# tdt_rereference.net
KiCad netlist of a schematic drawn in EAGLE
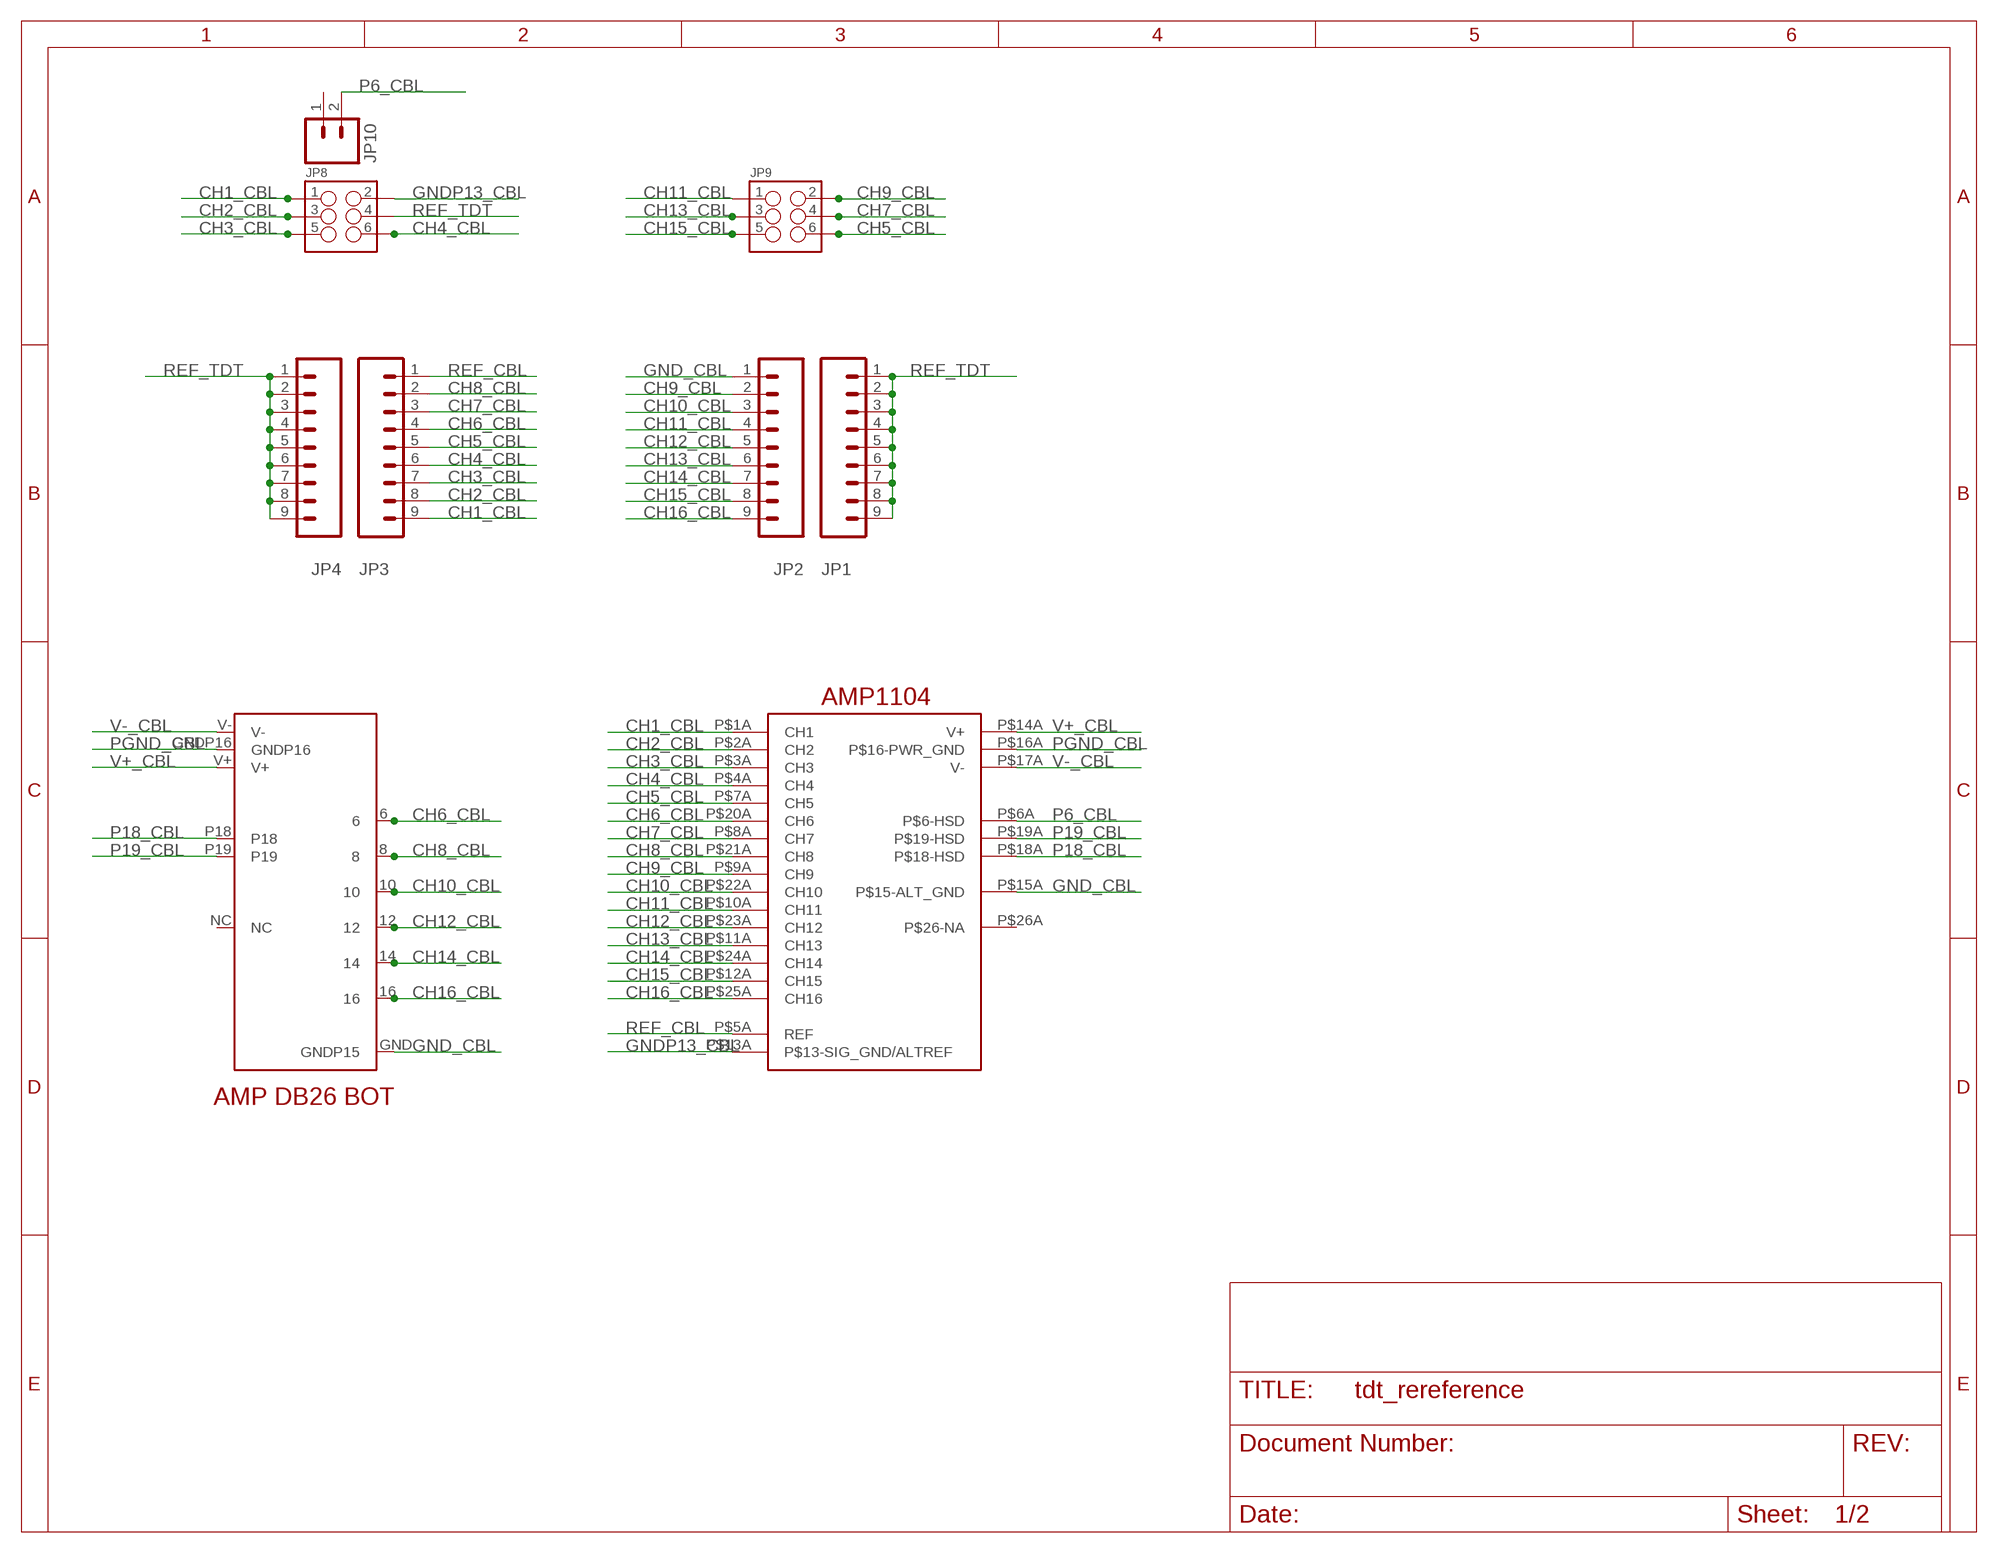
[diagram p0: schematic, sheet 1]
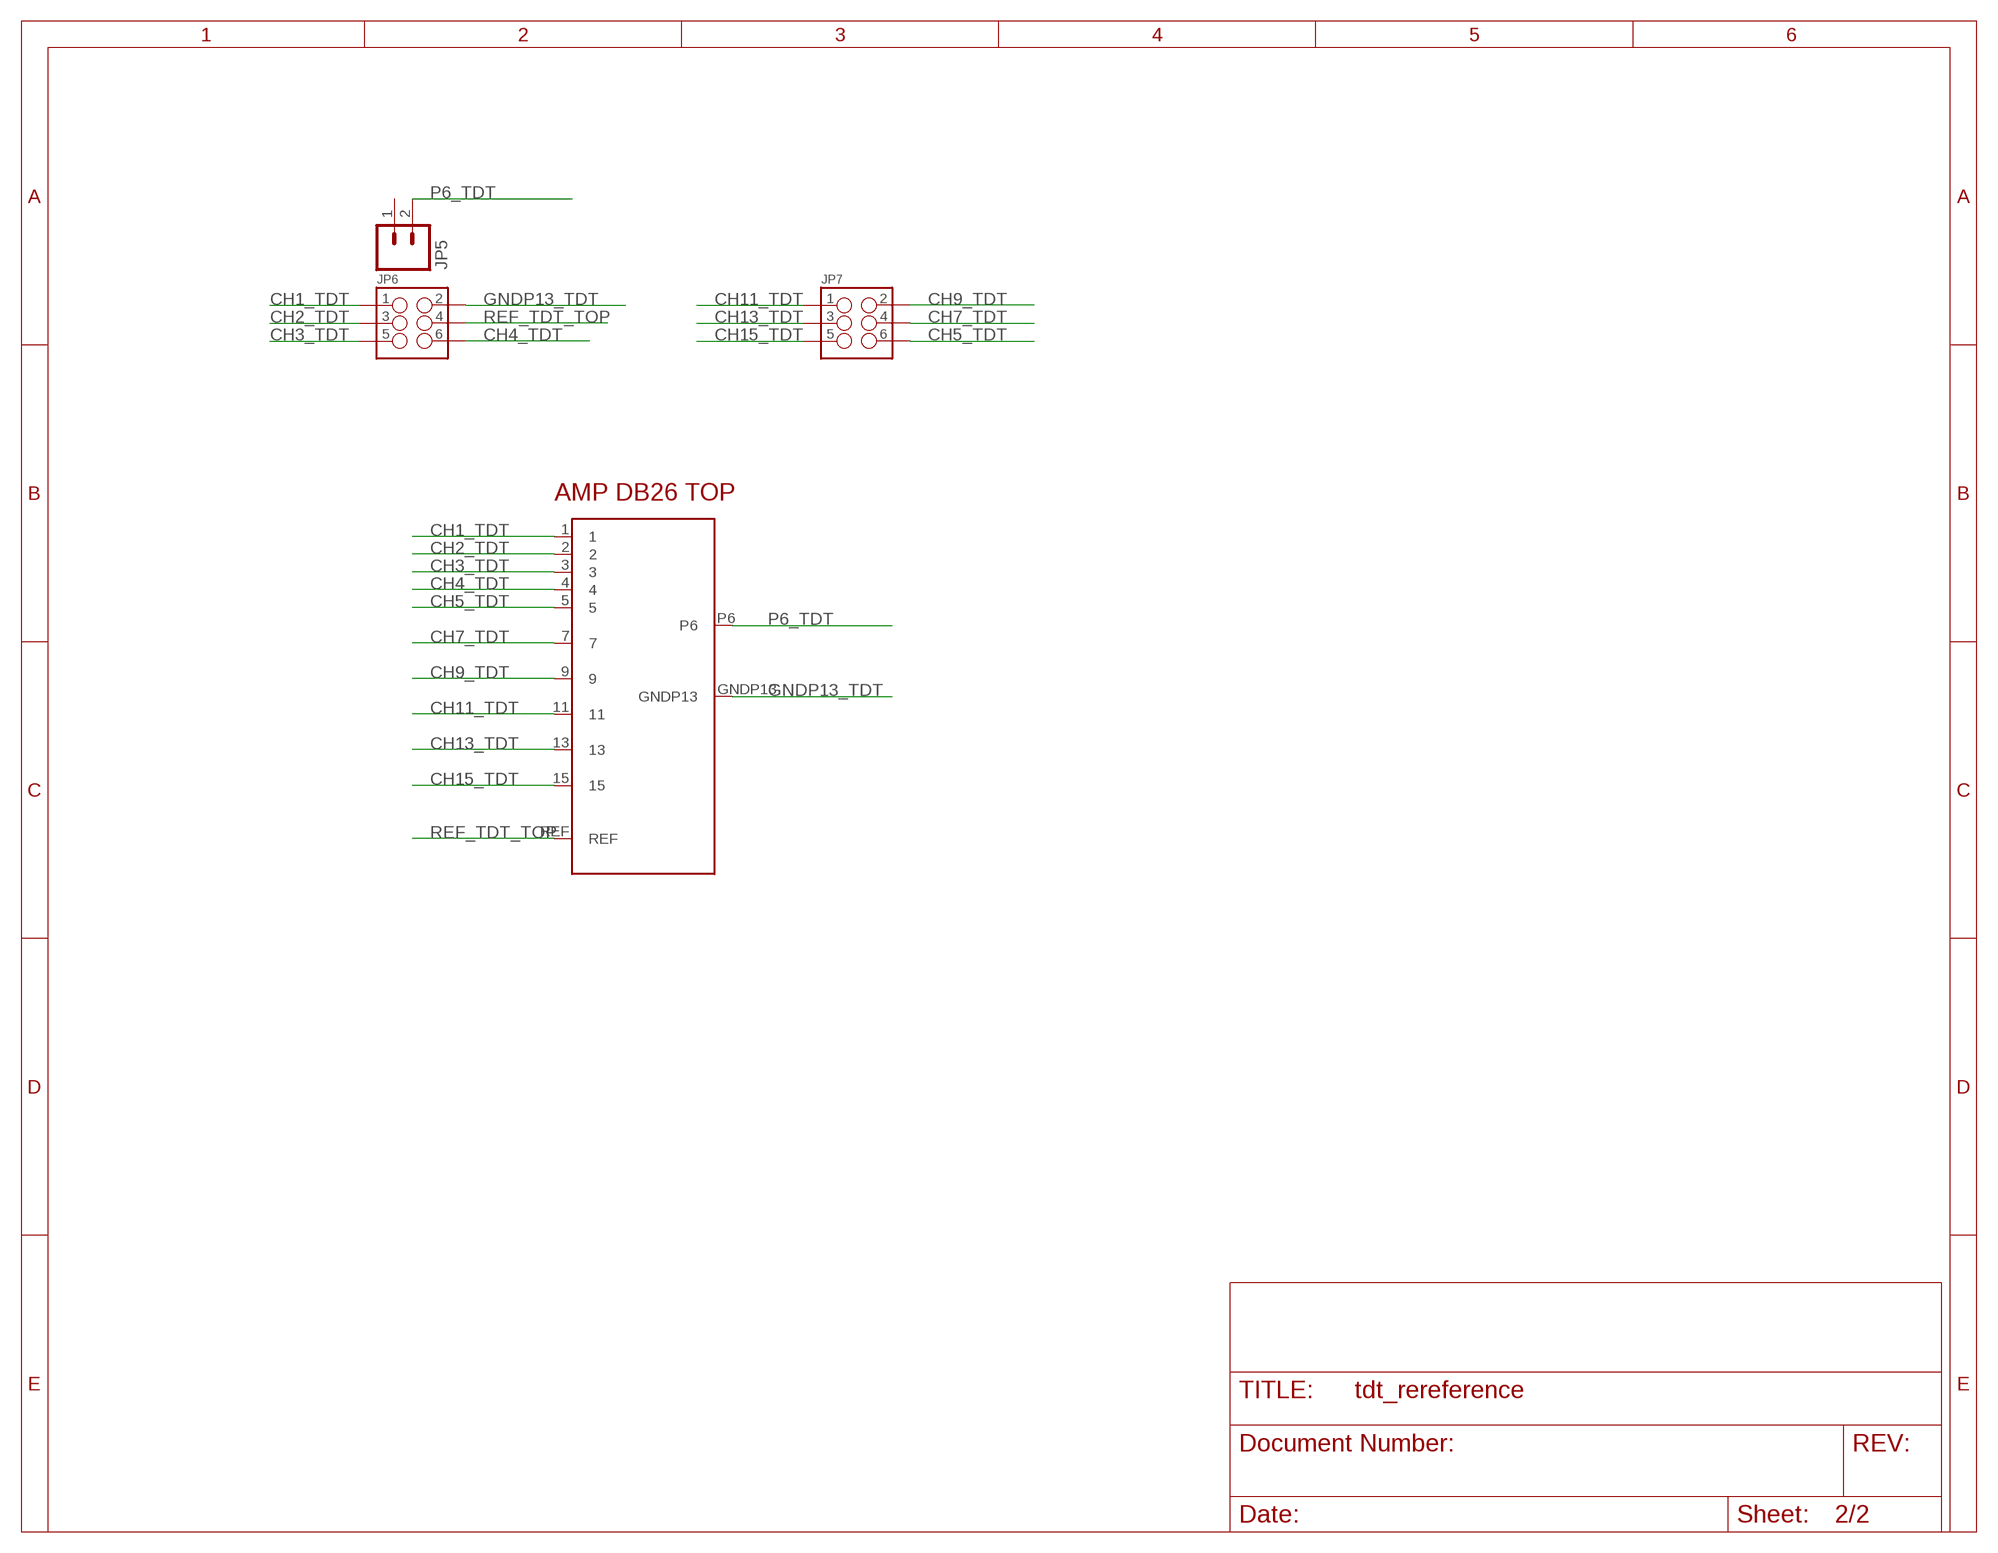
[diagram p1: schematic, sheet 2]

(export (version "E")
  (design (tool "Eeschema 10.0.6"))
  (components
    (comp (ref "JP5")
      (value "M02PTH")
      (footprint "eagle-import:1X02")
      (libsource (lib "eagle-import") (part "M02PTH"))
    )
    (comp (ref "JP6")
      (value "M03X22X3_SILK_MALE_PTH")
      (footprint "eagle-import:2X3")
      (libsource (lib "eagle-import") (part "M03X22X3_SILK_MALE_PTH"))
    )
    (comp (ref "JP7")
      (value "M03X22X3_SILK_MALE_PTH")
      (footprint "eagle-import:2X3")
      (libsource (lib "eagle-import") (part "M03X22X3_SILK_MALE_PTH"))
    )
    (comp (ref "U$2")
      (value "DB26-MALE-TOP")
      (footprint "eagle-import:DB26-MALE-TOP")
      (libsource (lib "eagle-import") (part "DB26-MALE-TOP"))
    )
    (comp (ref "JP1")
      (value "M09")
      (footprint "eagle-import:1X09")
      (libsource (lib "eagle-import") (part "M09"))
    )
    (comp (ref "JP2")
      (value "M09")
      (footprint "eagle-import:1X09")
      (libsource (lib "eagle-import") (part "M09"))
    )
    (comp (ref "JP3")
      (value "M09")
      (footprint "eagle-import:1X09")
      (libsource (lib "eagle-import") (part "M09"))
    )
    (comp (ref "JP4")
      (value "M09")
      (footprint "eagle-import:1X09")
      (libsource (lib "eagle-import") (part "M09"))
    )
    (comp (ref "JP8")
      (value "M03X22X3_SILK_MALE_PTH")
      (footprint "eagle-import:2X3")
      (libsource (lib "eagle-import") (part "M03X22X3_SILK_MALE_PTH"))
    )
    (comp (ref "JP9")
      (value "M03X22X3_SILK_MALE_PTH")
      (footprint "eagle-import:2X3")
      (libsource (lib "eagle-import") (part "M03X22X3_SILK_MALE_PTH"))
    )
    (comp (ref "JP10")
      (value "M02PTH")
      (footprint "eagle-import:1X02")
      (libsource (lib "eagle-import") (part "M02PTH"))
    )
    (comp (ref "U$1")
      (value "DB26-MALE-BOT")
      (footprint "eagle-import:DB26-MALE-BOT")
      (libsource (lib "eagle-import") (part "DB26-MALE-BOT"))
    )
    (comp (ref "U$3")
      (value "AMP1104")
      (footprint "eagle-import:AMP1104")
      (libsource (lib "eagle-import") (part "AMP1104"))
    )
  )
  (nets
    (net (code "1") (name "CH1_CBL") (class "Default")
      (node (ref "JP3") (pin "9") (pinfunction "9_9") (pintype "passive"))
      (node (ref "JP8") (pin "1") (pinfunction "1_1") (pintype "bidirectional"))
      (node (ref "U$3") (pin "P$1A") (pinfunction "CH1_P$1A") (pintype "bidirectional"))
    )
    (net (code "2") (name "CH1_TDT") (class "Default")
      (node (ref "JP6") (pin "1") (pinfunction "1_1") (pintype "bidirectional"))
      (node (ref "U$2") (pin "1") (pinfunction "1_1") (pintype "bidirectional"))
    )
    (net (code "3") (name "CH2_CBL") (class "Default")
      (node (ref "JP3") (pin "8") (pinfunction "8_8") (pintype "passive"))
      (node (ref "JP8") (pin "3") (pinfunction "3_3") (pintype "bidirectional"))
      (node (ref "U$3") (pin "P$2A") (pinfunction "CH2_P$2A") (pintype "bidirectional"))
    )
    (net (code "4") (name "CH2_TDT") (class "Default")
      (node (ref "JP6") (pin "3") (pinfunction "3_3") (pintype "bidirectional"))
      (node (ref "U$2") (pin "2") (pinfunction "2_2") (pintype "bidirectional"))
    )
    (net (code "5") (name "CH3_CBL") (class "Default")
      (node (ref "JP3") (pin "7") (pinfunction "7_7") (pintype "passive"))
      (node (ref "JP8") (pin "5") (pinfunction "5_5") (pintype "bidirectional"))
      (node (ref "U$3") (pin "P$3A") (pinfunction "CH3_P$3A") (pintype "bidirectional"))
    )
    (net (code "6") (name "CH3_TDT") (class "Default")
      (node (ref "JP6") (pin "5") (pinfunction "5_5") (pintype "bidirectional"))
      (node (ref "U$2") (pin "3") (pinfunction "3_3") (pintype "bidirectional"))
    )
    (net (code "7") (name "CH4_CBL") (class "Default")
      (node (ref "JP3") (pin "6") (pinfunction "6_6") (pintype "passive"))
      (node (ref "JP8") (pin "6") (pinfunction "6_6") (pintype "bidirectional"))
      (node (ref "U$3") (pin "P$4A") (pinfunction "CH4_P$4A") (pintype "bidirectional"))
    )
    (net (code "8") (name "CH4_TDT") (class "Default")
      (node (ref "JP6") (pin "6") (pinfunction "6_6") (pintype "bidirectional"))
      (node (ref "U$2") (pin "4") (pinfunction "4_4") (pintype "bidirectional"))
    )
    (net (code "9") (name "CH5_CBL") (class "Default")
      (node (ref "JP3") (pin "5") (pinfunction "5_5") (pintype "passive"))
      (node (ref "JP9") (pin "6") (pinfunction "6_6") (pintype "bidirectional"))
      (node (ref "U$3") (pin "P$7A") (pinfunction "CH5_P$7A") (pintype "bidirectional"))
    )
    (net (code "10") (name "CH5_TDT") (class "Default")
      (node (ref "JP7") (pin "6") (pinfunction "6_6") (pintype "bidirectional"))
      (node (ref "U$2") (pin "5") (pinfunction "5_5") (pintype "bidirectional"))
    )
    (net (code "11") (name "CH6_CBL") (class "Default")
      (node (ref "JP3") (pin "4") (pinfunction "4_4") (pintype "passive"))
      (node (ref "U$1") (pin "6") (pinfunction "6_6") (pintype "bidirectional"))
      (node (ref "U$3") (pin "P$20A") (pinfunction "CH6_P$20A") (pintype "bidirectional"))
    )
    (net (code "12") (name "CH7_CBL") (class "Default")
      (node (ref "JP3") (pin "3") (pinfunction "3_3") (pintype "passive"))
      (node (ref "JP9") (pin "4") (pinfunction "4_4") (pintype "bidirectional"))
      (node (ref "U$3") (pin "P$8A") (pinfunction "CH7_P$8A") (pintype "bidirectional"))
    )
    (net (code "13") (name "CH7_TDT") (class "Default")
      (node (ref "JP7") (pin "4") (pinfunction "4_4") (pintype "bidirectional"))
      (node (ref "U$2") (pin "7") (pinfunction "7_7") (pintype "bidirectional"))
    )
    (net (code "14") (name "CH8_CBL") (class "Default")
      (node (ref "JP3") (pin "2") (pinfunction "2_2") (pintype "passive"))
      (node (ref "U$1") (pin "8") (pinfunction "8_8") (pintype "bidirectional"))
      (node (ref "U$3") (pin "P$21A") (pinfunction "CH8_P$21A") (pintype "bidirectional"))
    )
    (net (code "15") (name "CH9_CBL") (class "Default")
      (node (ref "JP2") (pin "2") (pinfunction "2_2") (pintype "passive"))
      (node (ref "JP9") (pin "2") (pinfunction "2_2") (pintype "bidirectional"))
      (node (ref "U$3") (pin "P$9A") (pinfunction "CH9_P$9A") (pintype "bidirectional"))
    )
    (net (code "16") (name "CH9_TDT") (class "Default")
      (node (ref "JP7") (pin "2") (pinfunction "2_2") (pintype "bidirectional"))
      (node (ref "U$2") (pin "9") (pinfunction "9_9") (pintype "bidirectional"))
    )
    (net (code "17") (name "CH10_CBL") (class "Default")
      (node (ref "JP2") (pin "3") (pinfunction "3_3") (pintype "passive"))
      (node (ref "U$1") (pin "10") (pinfunction "10_10") (pintype "bidirectional"))
      (node (ref "U$3") (pin "P$22A") (pinfunction "CH10_P$22A") (pintype "bidirectional"))
    )
    (net (code "18") (name "CH11_CBL") (class "Default")
      (node (ref "JP2") (pin "4") (pinfunction "4_4") (pintype "passive"))
      (node (ref "JP9") (pin "1") (pinfunction "1_1") (pintype "bidirectional"))
      (node (ref "U$3") (pin "P$10A") (pinfunction "CH11_P$10A") (pintype "bidirectional"))
    )
    (net (code "19") (name "CH11_TDT") (class "Default")
      (node (ref "JP7") (pin "1") (pinfunction "1_1") (pintype "bidirectional"))
      (node (ref "U$2") (pin "11") (pinfunction "11_11") (pintype "bidirectional"))
    )
    (net (code "20") (name "CH12_CBL") (class "Default")
      (node (ref "JP2") (pin "5") (pinfunction "5_5") (pintype "passive"))
      (node (ref "U$1") (pin "12") (pinfunction "12_12") (pintype "bidirectional"))
      (node (ref "U$3") (pin "P$23A") (pinfunction "CH12_P$23A") (pintype "bidirectional"))
    )
    (net (code "21") (name "CH13_CBL") (class "Default")
      (node (ref "JP2") (pin "6") (pinfunction "6_6") (pintype "passive"))
      (node (ref "JP9") (pin "3") (pinfunction "3_3") (pintype "bidirectional"))
      (node (ref "U$3") (pin "P$11A") (pinfunction "CH13_P$11A") (pintype "bidirectional"))
    )
    (net (code "22") (name "CH13_TDT") (class "Default")
      (node (ref "JP7") (pin "3") (pinfunction "3_3") (pintype "bidirectional"))
      (node (ref "U$2") (pin "13") (pinfunction "13_13") (pintype "bidirectional"))
    )
    (net (code "23") (name "CH14_CBL") (class "Default")
      (node (ref "JP2") (pin "7") (pinfunction "7_7") (pintype "passive"))
      (node (ref "U$1") (pin "14") (pinfunction "14_14") (pintype "bidirectional"))
      (node (ref "U$3") (pin "P$24A") (pinfunction "CH14_P$24A") (pintype "bidirectional"))
    )
    (net (code "24") (name "CH15_CBL") (class "Default")
      (node (ref "JP2") (pin "8") (pinfunction "8_8") (pintype "passive"))
      (node (ref "JP9") (pin "5") (pinfunction "5_5") (pintype "bidirectional"))
      (node (ref "U$3") (pin "P$12A") (pinfunction "CH15_P$12A") (pintype "bidirectional"))
    )
    (net (code "25") (name "CH15_TDT") (class "Default")
      (node (ref "JP7") (pin "5") (pinfunction "5_5") (pintype "bidirectional"))
      (node (ref "U$2") (pin "15") (pinfunction "15_15") (pintype "bidirectional"))
    )
    (net (code "26") (name "CH16_CBL") (class "Default")
      (node (ref "JP2") (pin "9") (pinfunction "9_9") (pintype "passive"))
      (node (ref "U$1") (pin "16") (pinfunction "16_16") (pintype "bidirectional"))
      (node (ref "U$3") (pin "P$25A") (pinfunction "CH16_P$25A") (pintype "bidirectional"))
    )
    (net (code "27") (name "GNDP13_CBL") (class "Default")
      (node (ref "JP8") (pin "2") (pinfunction "2_2") (pintype "bidirectional"))
      (node (ref "U$3") (pin "P$13A") (pinfunction "P$13-SIG_GND/ALTREF_P$13A") (pintype "bidirectional"))
    )
    (net (code "28") (name "GNDP13_TDT") (class "Default")
      (node (ref "JP6") (pin "2") (pinfunction "2_2") (pintype "bidirectional"))
      (node (ref "U$2") (pin "GNDP13") (pinfunction "GNDP13_GNDP13") (pintype "bidirectional"))
    )
    (net (code "29") (name "GND_CBL") (class "Default")
      (node (ref "JP2") (pin "1") (pinfunction "1_1") (pintype "passive"))
      (node (ref "U$1") (pin "GND") (pinfunction "GNDP15_GND") (pintype "bidirectional"))
      (node (ref "U$3") (pin "P$15A") (pinfunction "P$15-ALT_GND_P$15A") (pintype "bidirectional"))
    )
    (net (code "30") (name "P6_CBL") (class "Default")
      (node (ref "JP10") (pin "2") (pinfunction "2_2") (pintype "passive"))
      (node (ref "U$3") (pin "P$6A") (pinfunction "P$6-HSD_P$6A") (pintype "bidirectional"))
    )
    (net (code "31") (name "P6_TDT") (class "Default")
      (node (ref "JP5") (pin "2") (pinfunction "2_2") (pintype "passive"))
      (node (ref "U$2") (pin "P6") (pinfunction "P6_P6") (pintype "bidirectional"))
    )
    (net (code "32") (name "P18_CBL") (class "Default")
      (node (ref "U$1") (pin "P18") (pinfunction "P18_P18") (pintype "bidirectional"))
      (node (ref "U$3") (pin "P$18A") (pinfunction "P$18-HSD_P$18A") (pintype "bidirectional"))
    )
    (net (code "33") (name "P19_CBL") (class "Default")
      (node (ref "U$1") (pin "P19") (pinfunction "P19_P19") (pintype "bidirectional"))
      (node (ref "U$3") (pin "P$19A") (pinfunction "P$19-HSD_P$19A") (pintype "bidirectional"))
    )
    (net (code "34") (name "PGND_CBL") (class "Default")
      (node (ref "U$1") (pin "GNDP16") (pinfunction "GNDP16_GNDP16") (pintype "bidirectional"))
      (node (ref "U$3") (pin "P$16A") (pinfunction "P$16-PWR_GND_P$16A") (pintype "bidirectional"))
    )
    (net (code "35") (name "REF_CBL") (class "Default")
      (node (ref "JP3") (pin "1") (pinfunction "1_1") (pintype "passive"))
      (node (ref "U$3") (pin "P$5A") (pinfunction "REF_P$5A") (pintype "bidirectional"))
    )
    (net (code "36") (name "REF_TDT") (class "Default")
      (node (ref "JP1") (pin "1") (pinfunction "1_1") (pintype "passive"))
      (node (ref "JP1") (pin "2") (pinfunction "2_2") (pintype "passive"))
      (node (ref "JP1") (pin "3") (pinfunction "3_3") (pintype "passive"))
      (node (ref "JP1") (pin "4") (pinfunction "4_4") (pintype "passive"))
      (node (ref "JP1") (pin "5") (pinfunction "5_5") (pintype "passive"))
      (node (ref "JP1") (pin "6") (pinfunction "6_6") (pintype "passive"))
      (node (ref "JP1") (pin "7") (pinfunction "7_7") (pintype "passive"))
      (node (ref "JP1") (pin "8") (pinfunction "8_8") (pintype "passive"))
      (node (ref "JP1") (pin "9") (pinfunction "9_9") (pintype "passive"))
      (node (ref "JP4") (pin "1") (pinfunction "1_1") (pintype "passive"))
      (node (ref "JP4") (pin "2") (pinfunction "2_2") (pintype "passive"))
      (node (ref "JP4") (pin "3") (pinfunction "3_3") (pintype "passive"))
      (node (ref "JP4") (pin "4") (pinfunction "4_4") (pintype "passive"))
      (node (ref "JP4") (pin "5") (pinfunction "5_5") (pintype "passive"))
      (node (ref "JP4") (pin "6") (pinfunction "6_6") (pintype "passive"))
      (node (ref "JP4") (pin "7") (pinfunction "7_7") (pintype "passive"))
      (node (ref "JP4") (pin "8") (pinfunction "8_8") (pintype "passive"))
      (node (ref "JP4") (pin "9") (pinfunction "9_9") (pintype "passive"))
      (node (ref "JP8") (pin "4") (pinfunction "4_4") (pintype "bidirectional"))
    )
    (net (code "37") (name "REF_TDT_TOP") (class "Default")
      (node (ref "JP6") (pin "4") (pinfunction "4_4") (pintype "bidirectional"))
      (node (ref "U$2") (pin "REF") (pinfunction "REF_REF") (pintype "bidirectional"))
    )
    (net (code "38") (name "V+_CBL") (class "Default")
      (node (ref "U$1") (pin "V+") (pinfunction "V+_V+") (pintype "bidirectional"))
      (node (ref "U$3") (pin "P$14A") (pinfunction "V+_P$14A") (pintype "bidirectional"))
    )
    (net (code "39") (name "V-_CBL") (class "Default")
      (node (ref "U$1") (pin "V-") (pinfunction "V-_V-") (pintype "bidirectional"))
      (node (ref "U$3") (pin "P$17A") (pinfunction "V-_P$17A") (pintype "bidirectional"))
    )
    (net (code "40") (name "unconnected-(JP5-Pad1)") (class "Default")
      (node (ref "JP5") (pin "1") (pinfunction "1_1") (pintype "passive"))
    )
    (net (code "41") (name "unconnected-(JP10-Pad1)") (class "Default")
      (node (ref "JP10") (pin "1") (pinfunction "1_1") (pintype "passive"))
    )
    (net (code "42") (name "unconnected-(U$1-PadNC)") (class "Default")
      (node (ref "U$1") (pin "NC") (pinfunction "NC_NC") (pintype "bidirectional"))
    )
    (net (code "43") (name "unconnected-(U$3-P$26-NA-PadP$26A)") (class "Default")
      (node (ref "U$3") (pin "P$26A") (pinfunction "P$26-NA_P$26A") (pintype "bidirectional"))
    )
  )
)
